# earing.net
KiCad netlist of a schematic drawn in EAGLE
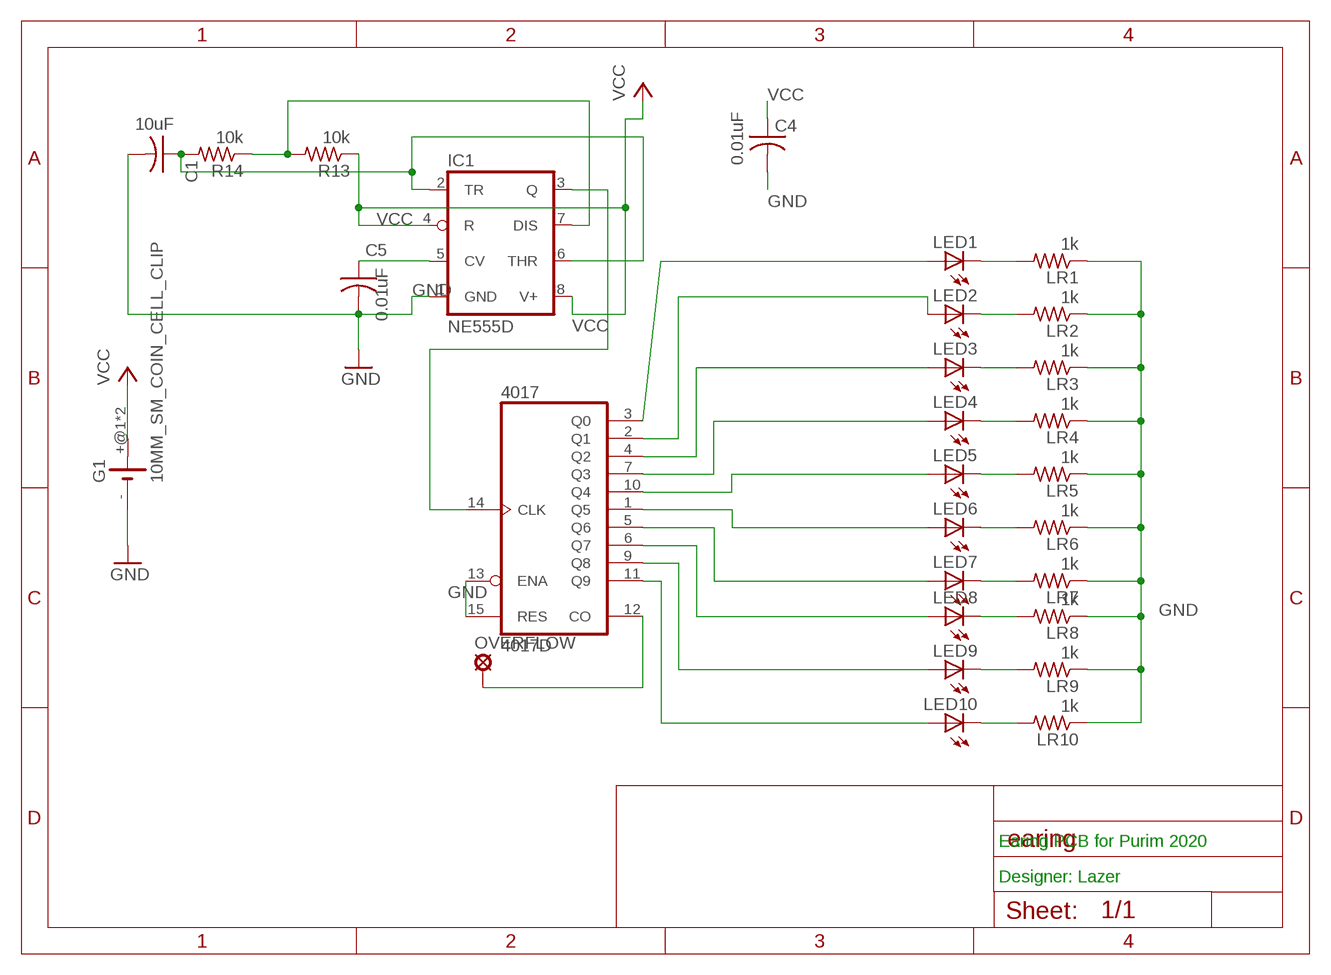
[diagram p0: schematic, sheet 1]

(export (version "E")
  (design (tool "Eeschema 10.0.6"))
  (components
    (comp (ref "4017")
      (value "4017D")
      (footprint "eagle-import:SO16")
      (libsource (lib "eagle-import") (part "4017D"))
    )
    (comp (ref "C1")
      (value "10uF")
      (footprint "eagle-import:C0805")
      (libsource (lib "eagle-import") (part "C-USC0805"))
    )
    (comp (ref "C4")
      (value "0.01uF")
      (footprint "eagle-import:C0805")
      (libsource (lib "eagle-import") (part "C-USC0805"))
    )
    (comp (ref "C5")
      (value "0.01uF")
      (footprint "eagle-import:C0805")
      (libsource (lib "eagle-import") (part "C-USC0805"))
    )
    (comp (ref "G1")
      (value "10MM_SM_COIN_CELL_CLIP")
      (footprint "eagle-import:10MM_SM_COIN_CELL_CLIP")
      (libsource (lib "eagle-import") (part "10MM_SM_COIN_CELL_CLIP"))
    )
    (comp (ref "IC1")
      (value "NE555D")
      (footprint "eagle-import:SO08")
      (libsource (lib "eagle-import") (part "555DNE"))
    )
    (comp (ref "LED1")
      (value "LEDCHIP-LED0805")
      (footprint "eagle-import:CHIP-LED0805")
      (libsource (lib "eagle-import") (part "LEDCHIP-LED0805"))
    )
    (comp (ref "LED2")
      (value "LEDCHIP-LED0805")
      (footprint "eagle-import:CHIP-LED0805")
      (libsource (lib "eagle-import") (part "LEDCHIP-LED0805"))
    )
    (comp (ref "LED3")
      (value "LEDCHIP-LED0805")
      (footprint "eagle-import:CHIP-LED0805")
      (libsource (lib "eagle-import") (part "LEDCHIP-LED0805"))
    )
    (comp (ref "LED4")
      (value "LEDCHIP-LED0805")
      (footprint "eagle-import:CHIP-LED0805")
      (libsource (lib "eagle-import") (part "LEDCHIP-LED0805"))
    )
    (comp (ref "LED5")
      (value "LEDCHIP-LED0805")
      (footprint "eagle-import:CHIP-LED0805")
      (libsource (lib "eagle-import") (part "LEDCHIP-LED0805"))
    )
    (comp (ref "LED6")
      (value "LEDCHIP-LED0805")
      (footprint "eagle-import:CHIP-LED0805")
      (libsource (lib "eagle-import") (part "LEDCHIP-LED0805"))
    )
    (comp (ref "LED7")
      (value "LEDCHIP-LED0805")
      (footprint "eagle-import:CHIP-LED0805")
      (libsource (lib "eagle-import") (part "LEDCHIP-LED0805"))
    )
    (comp (ref "LED8")
      (value "LEDCHIP-LED0805")
      (footprint "eagle-import:CHIP-LED0805")
      (libsource (lib "eagle-import") (part "LEDCHIP-LED0805"))
    )
    (comp (ref "LED9")
      (value "LEDCHIP-LED0805")
      (footprint "eagle-import:CHIP-LED0805")
      (libsource (lib "eagle-import") (part "LEDCHIP-LED0805"))
    )
    (comp (ref "LED10")
      (value "LEDCHIP-LED0805")
      (footprint "eagle-import:CHIP-LED0805")
      (libsource (lib "eagle-import") (part "LEDCHIP-LED0805"))
    )
    (comp (ref "LR1")
      (value "1k")
      (footprint "eagle-import:M0805")
      (libsource (lib "eagle-import") (part "R-US_M0805"))
    )
    (comp (ref "LR2")
      (value "1k")
      (footprint "eagle-import:M0805")
      (libsource (lib "eagle-import") (part "R-US_M0805"))
    )
    (comp (ref "LR3")
      (value "1k")
      (footprint "eagle-import:M0805")
      (libsource (lib "eagle-import") (part "R-US_M0805"))
    )
    (comp (ref "LR4")
      (value "1k")
      (footprint "eagle-import:M0805")
      (libsource (lib "eagle-import") (part "R-US_M0805"))
    )
    (comp (ref "LR5")
      (value "1k")
      (footprint "eagle-import:M0805")
      (libsource (lib "eagle-import") (part "R-US_M0805"))
    )
    (comp (ref "LR6")
      (value "1k")
      (footprint "eagle-import:M0805")
      (libsource (lib "eagle-import") (part "R-US_M0805"))
    )
    (comp (ref "LR7")
      (value "1k")
      (footprint "eagle-import:M0805")
      (libsource (lib "eagle-import") (part "R-US_M0805"))
    )
    (comp (ref "LR8")
      (value "1k")
      (footprint "eagle-import:M0805")
      (libsource (lib "eagle-import") (part "R-US_M0805"))
    )
    (comp (ref "LR9")
      (value "1k")
      (footprint "eagle-import:M0805")
      (libsource (lib "eagle-import") (part "R-US_M0805"))
    )
    (comp (ref "LR10")
      (value "1k")
      (footprint "eagle-import:M0805")
      (libsource (lib "eagle-import") (part "R-US_M0805"))
    )
    (comp (ref "OVERFLOW")
      (value "LSP10")
      (footprint "eagle-import:LSP10")
      (libsource (lib "eagle-import") (part "LSP10"))
    )
    (comp (ref "R13")
      (value "10k")
      (footprint "eagle-import:M0805")
      (libsource (lib "eagle-import") (part "R-US_M0805"))
    )
    (comp (ref "R14")
      (value "10k")
      (footprint "eagle-import:M0805")
      (libsource (lib "eagle-import") (part "R-US_M0805"))
    )
  )
  (nets
    (net (code "1") (name "GND") (class "Default")
      (node (ref "4017") (pin "13") (pinfunction "ENA_13") (pintype "input"))
      (node (ref "4017") (pin "15") (pinfunction "RES_15") (pintype "input"))
      (node (ref "C1") (pin "2") (pinfunction "2_2") (pintype "passive"))
      (node (ref "C4") (pin "2") (pinfunction "2_2") (pintype "passive"))
      (node (ref "C5") (pin "2") (pinfunction "2_2") (pintype "passive"))
      (node (ref "G1") (pin "-") (pinfunction "-_-") (pintype "passive"))
      (node (ref "IC1") (pin "1") (pinfunction "GND_1") (pintype "power_in"))
      (node (ref "LR1") (pin "1") (pinfunction "1_1") (pintype "passive"))
      (node (ref "LR10") (pin "1") (pinfunction "1_1") (pintype "passive"))
      (node (ref "LR2") (pin "1") (pinfunction "1_1") (pintype "passive"))
      (node (ref "LR3") (pin "1") (pinfunction "1_1") (pintype "passive"))
      (node (ref "LR4") (pin "1") (pinfunction "1_1") (pintype "passive"))
      (node (ref "LR5") (pin "1") (pinfunction "1_1") (pintype "passive"))
      (node (ref "LR6") (pin "1") (pinfunction "1_1") (pintype "passive"))
      (node (ref "LR7") (pin "1") (pinfunction "1_1") (pintype "passive"))
      (node (ref "LR8") (pin "1") (pinfunction "1_1") (pintype "passive"))
      (node (ref "LR9") (pin "1") (pinfunction "1_1") (pintype "passive"))
    )
    (net (code "2") (name "Net-(4017A-CLK)") (class "Default")
      (node (ref "4017") (pin "14") (pinfunction "CLK_14") (pintype "input"))
      (node (ref "IC1") (pin "3") (pinfunction "Q_3") (pintype "output"))
    )
    (net (code "3") (name "Net-(4017A-CO)") (class "Default")
      (node (ref "4017") (pin "12") (pinfunction "CO_12") (pintype "output"))
      (node (ref "OVERFLOW") (pin "MP") (pinfunction "MP_MP") (pintype "passive"))
    )
    (net (code "4") (name "Net-(4017A-Q0)") (class "Default")
      (node (ref "4017") (pin "3") (pinfunction "Q0_3") (pintype "output"))
      (node (ref "LED1") (pin "A") (pinfunction "A_A") (pintype "passive"))
    )
    (net (code "5") (name "Net-(4017A-Q1)") (class "Default")
      (node (ref "4017") (pin "2") (pinfunction "Q1_2") (pintype "output"))
      (node (ref "LED2") (pin "A") (pinfunction "A_A") (pintype "passive"))
    )
    (net (code "6") (name "Net-(4017A-Q2)") (class "Default")
      (node (ref "4017") (pin "4") (pinfunction "Q2_4") (pintype "output"))
      (node (ref "LED3") (pin "A") (pinfunction "A_A") (pintype "passive"))
    )
    (net (code "7") (name "Net-(4017A-Q3)") (class "Default")
      (node (ref "4017") (pin "7") (pinfunction "Q3_7") (pintype "output"))
      (node (ref "LED4") (pin "A") (pinfunction "A_A") (pintype "passive"))
    )
    (net (code "8") (name "Net-(4017A-Q4)") (class "Default")
      (node (ref "4017") (pin "10") (pinfunction "Q4_10") (pintype "output"))
      (node (ref "LED5") (pin "A") (pinfunction "A_A") (pintype "passive"))
    )
    (net (code "9") (name "Net-(4017A-Q5)") (class "Default")
      (node (ref "4017") (pin "1") (pinfunction "Q5_1") (pintype "output"))
      (node (ref "LED6") (pin "A") (pinfunction "A_A") (pintype "passive"))
    )
    (net (code "10") (name "Net-(4017A-Q6)") (class "Default")
      (node (ref "4017") (pin "5") (pinfunction "Q6_5") (pintype "output"))
      (node (ref "LED7") (pin "A") (pinfunction "A_A") (pintype "passive"))
    )
    (net (code "11") (name "Net-(4017A-Q7)") (class "Default")
      (node (ref "4017") (pin "6") (pinfunction "Q7_6") (pintype "output"))
      (node (ref "LED8") (pin "A") (pinfunction "A_A") (pintype "passive"))
    )
    (net (code "12") (name "Net-(4017A-Q8)") (class "Default")
      (node (ref "4017") (pin "9") (pinfunction "Q8_9") (pintype "output"))
      (node (ref "LED9") (pin "A") (pinfunction "A_A") (pintype "passive"))
    )
    (net (code "13") (name "Net-(4017A-Q9)") (class "Default")
      (node (ref "4017") (pin "11") (pinfunction "Q9_11") (pintype "output"))
      (node (ref "LED10") (pin "A") (pinfunction "A_A") (pintype "passive"))
    )
    (net (code "14") (name "Net-(IC1-CV)") (class "Default")
      (node (ref "C5") (pin "1") (pinfunction "1_1") (pintype "passive"))
      (node (ref "IC1") (pin "5") (pinfunction "CV_5") (pintype "input"))
    )
    (net (code "15") (name "Net-(IC1-DIS)") (class "Default")
      (node (ref "IC1") (pin "7") (pinfunction "DIS_7") (pintype "input"))
      (node (ref "R13") (pin "2") (pinfunction "2_2") (pintype "passive"))
      (node (ref "R14") (pin "1") (pinfunction "1_1") (pintype "passive"))
    )
    (net (code "16") (name "Net-(IC1-THR)") (class "Default")
      (node (ref "C1") (pin "1") (pinfunction "1_1") (pintype "passive"))
      (node (ref "IC1") (pin "2") (pinfunction "TR_2") (pintype "input"))
      (node (ref "IC1") (pin "6") (pinfunction "THR_6") (pintype "input"))
      (node (ref "R14") (pin "2") (pinfunction "2_2") (pintype "passive"))
    )
    (net (code "17") (name "Net-(LED1-PadC)") (class "Default")
      (node (ref "LED1") (pin "C") (pinfunction "C_C") (pintype "passive"))
      (node (ref "LR1") (pin "2") (pinfunction "2_2") (pintype "passive"))
    )
    (net (code "18") (name "Net-(LED2-PadC)") (class "Default")
      (node (ref "LED2") (pin "C") (pinfunction "C_C") (pintype "passive"))
      (node (ref "LR2") (pin "2") (pinfunction "2_2") (pintype "passive"))
    )
    (net (code "19") (name "Net-(LED3-PadC)") (class "Default")
      (node (ref "LED3") (pin "C") (pinfunction "C_C") (pintype "passive"))
      (node (ref "LR3") (pin "2") (pinfunction "2_2") (pintype "passive"))
    )
    (net (code "20") (name "Net-(LED4-PadC)") (class "Default")
      (node (ref "LED4") (pin "C") (pinfunction "C_C") (pintype "passive"))
      (node (ref "LR4") (pin "2") (pinfunction "2_2") (pintype "passive"))
    )
    (net (code "21") (name "Net-(LED5-PadC)") (class "Default")
      (node (ref "LED5") (pin "C") (pinfunction "C_C") (pintype "passive"))
      (node (ref "LR5") (pin "2") (pinfunction "2_2") (pintype "passive"))
    )
    (net (code "22") (name "Net-(LED6-PadC)") (class "Default")
      (node (ref "LED6") (pin "C") (pinfunction "C_C") (pintype "passive"))
      (node (ref "LR6") (pin "2") (pinfunction "2_2") (pintype "passive"))
    )
    (net (code "23") (name "Net-(LED7-PadC)") (class "Default")
      (node (ref "LED7") (pin "C") (pinfunction "C_C") (pintype "passive"))
      (node (ref "LR7") (pin "2") (pinfunction "2_2") (pintype "passive"))
    )
    (net (code "24") (name "Net-(LED8-PadC)") (class "Default")
      (node (ref "LED8") (pin "C") (pinfunction "C_C") (pintype "passive"))
      (node (ref "LR8") (pin "2") (pinfunction "2_2") (pintype "passive"))
    )
    (net (code "25") (name "Net-(LED9-PadC)") (class "Default")
      (node (ref "LED9") (pin "C") (pinfunction "C_C") (pintype "passive"))
      (node (ref "LR9") (pin "2") (pinfunction "2_2") (pintype "passive"))
    )
    (net (code "26") (name "Net-(LED10-PadC)") (class "Default")
      (node (ref "LED10") (pin "C") (pinfunction "C_C") (pintype "passive"))
      (node (ref "LR10") (pin "2") (pinfunction "2_2") (pintype "passive"))
    )
    (net (code "27") (name "VCC") (class "Default")
      (node (ref "C4") (pin "1") (pinfunction "1_1") (pintype "passive"))
      (node (ref "G1") (pin "+@1") (pinfunction "+_+@1") (pintype "passive"))
      (node (ref "G1") (pin "+@2") (pinfunction "+_+@2") (pintype "passive"))
      (node (ref "IC1") (pin "4") (pinfunction "R_4") (pintype "input"))
      (node (ref "IC1") (pin "8") (pinfunction "V+_8") (pintype "power_in"))
      (node (ref "R13") (pin "1") (pinfunction "1_1") (pintype "passive"))
    )
  )
)
